# ADC.net
KiCad netlist of a schematic drawn in Altium Designer
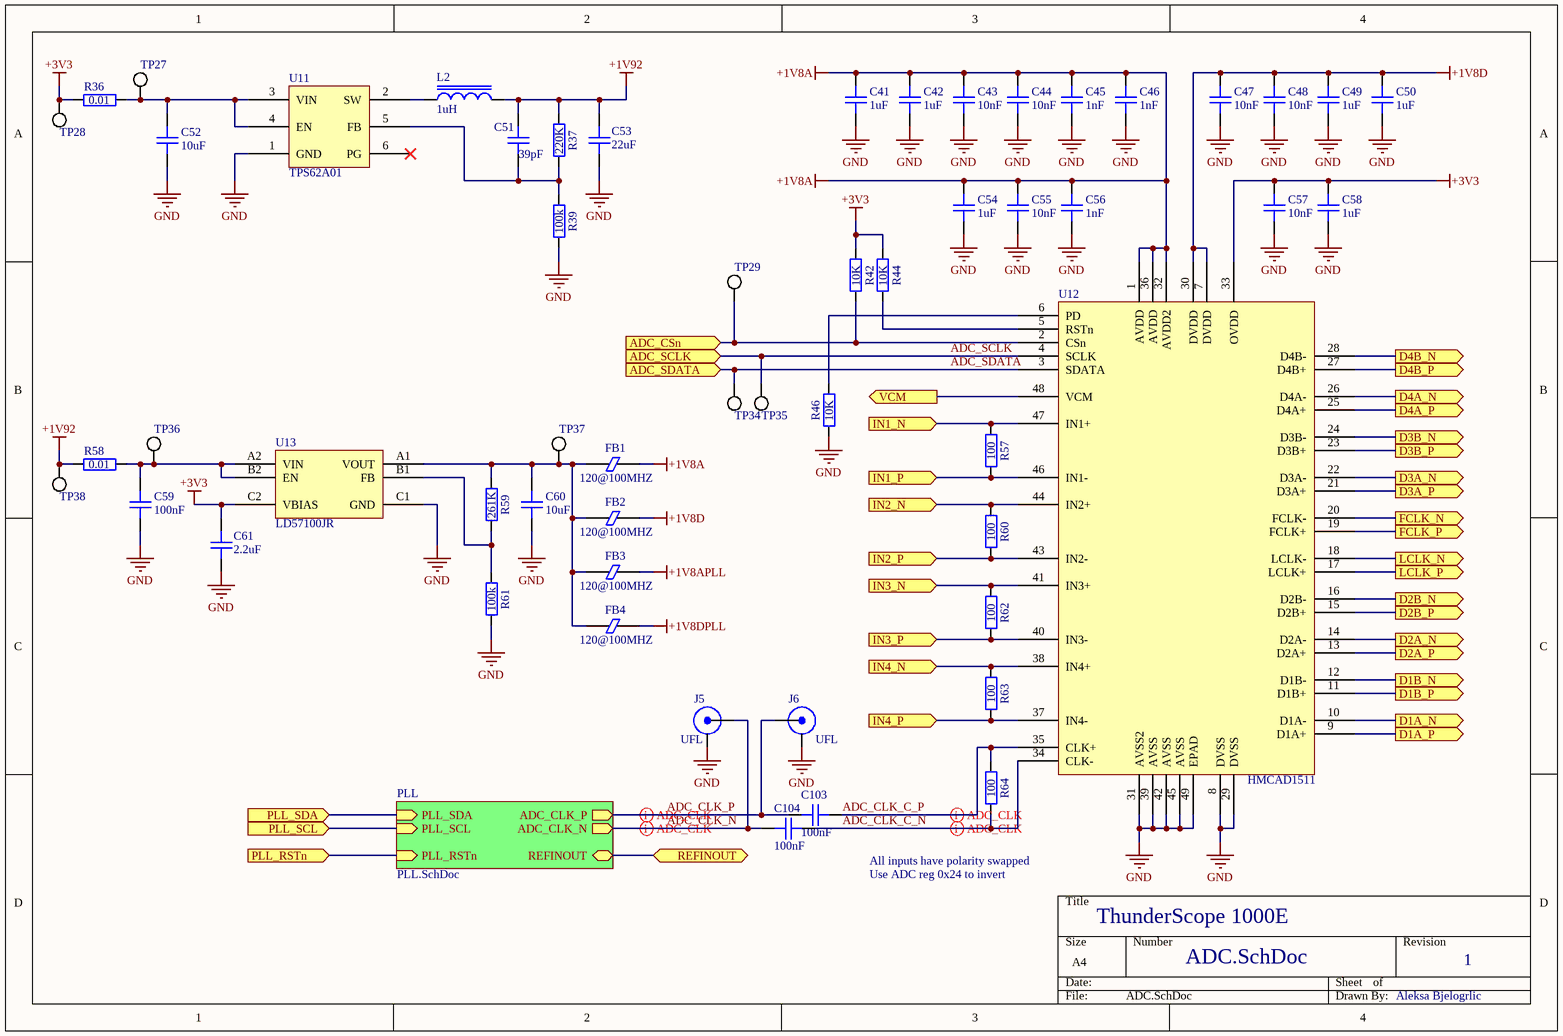
[diagram p0: ADC.SchDoc]

(export (version "E")
  (design (tool "Eeschema 10.0.6"))
  (components
    (comp (ref "C41")
      (value "1uF")
      (footprint "GEN_C_0402")
      (libsource (lib "DSO") (part "CAP 1uF 25V X5R 0402"))
    )
    (comp (ref "C42")
      (value "1uF")
      (footprint "GEN_C_0402")
      (libsource (lib "DSO") (part "CAP 1uF 25V X5R 0402"))
    )
    (comp (ref "C43")
      (value "10nF")
      (footprint "GEN_C_0402")
      (libsource (lib "DSO") (part "CAP 10nF 50V X7R 0402"))
    )
    (comp (ref "C44")
      (value "10nF")
      (footprint "GEN_C_0402")
      (libsource (lib "DSO") (part "CAP 10nF 50V X7R 0402"))
    )
    (comp (ref "C45")
      (value "1nF")
      (footprint "GEN_C_0402")
      (libsource (lib "DSO") (part "CAP 1nF 50V C0G 0402"))
    )
    (comp (ref "C46")
      (value "1nF")
      (footprint "GEN_C_0402")
      (libsource (lib "DSO") (part "CAP 1nF 50V C0G 0402"))
    )
    (comp (ref "C47")
      (value "10nF")
      (footprint "GEN_C_0402")
      (libsource (lib "DSO") (part "CAP 10nF 50V X7R 0402"))
    )
    (comp (ref "C48")
      (value "10nF")
      (footprint "GEN_C_0402")
      (libsource (lib "DSO") (part "CAP 10nF 50V X7R 0402"))
    )
    (comp (ref "C49")
      (value "1uF")
      (footprint "GEN_C_0402")
      (libsource (lib "DSO") (part "CAP 1uF 25V X5R 0402"))
    )
    (comp (ref "C50")
      (value "1uF")
      (footprint "GEN_C_0402")
      (libsource (lib "DSO") (part "CAP 1uF 25V X5R 0402"))
    )
    (comp (ref "C51")
      (value "39pF")
      (footprint "GEN_C_0402")
      (libsource (lib "DSO") (part "CAP 39pF 50V C0G 0402"))
    )
    (comp (ref "C52")
      (value "10uF")
      (footprint "GEN_C_0603")
      (libsource (lib "DSO") (part "CAP 10uF 10V X5R 0603"))
    )
    (comp (ref "C53")
      (value "22uF")
      (footprint "GEN_C_0805")
      (libsource (lib "DSO") (part "CAP 22uF 25V X5R 0805"))
    )
    (comp (ref "C54")
      (value "1uF")
      (footprint "GEN_C_0402")
      (libsource (lib "DSO") (part "CAP 1uF 25V X5R 0402"))
    )
    (comp (ref "C55")
      (value "10nF")
      (footprint "GEN_C_0402")
      (libsource (lib "DSO") (part "CAP 10nF 50V X7R 0402"))
    )
    (comp (ref "C56")
      (value "1nF")
      (footprint "GEN_C_0402")
      (libsource (lib "DSO") (part "CAP 1nF 50V C0G 0402"))
    )
    (comp (ref "C57")
      (value "10nF")
      (footprint "GEN_C_0402")
      (libsource (lib "DSO") (part "CAP 10nF 50V X7R 0402"))
    )
    (comp (ref "C58")
      (value "1uF")
      (footprint "GEN_C_0402")
      (libsource (lib "DSO") (part "CAP 1uF 25V X5R 0402"))
    )
    (comp (ref "C59")
      (value "100nF")
      (footprint "GEN_C_0402")
      (libsource (lib "DSO") (part "CAP 100nF 16V X7R 0402"))
    )
    (comp (ref "C60")
      (value "10uF")
      (footprint "GEN_C_0603")
      (libsource (lib "DSO") (part "CAP 10uF 10V X5R 0603"))
    )
    (comp (ref "C61")
      (value "2.2uF")
      (footprint "GEN_C_0402")
      (libsource (lib "DSO") (part "CAP 2.2uF 10V X5R 0402"))
    )
    (comp (ref "C103")
      (value "100nF")
      (footprint "GEN_C_0402")
      (libsource (lib "DSO") (part "CAP 100nF 16V X7R 0402"))
    )
    (comp (ref "C104")
      (value "100nF")
      (footprint "GEN_C_0402")
      (libsource (lib "DSO") (part "CAP 100nF 16V X7R 0402"))
    )
    (comp (ref "FB1")
      (value "120@100MHZ")
      (footprint "GEN_R_0402")
      (libsource (lib "DSO") (part "FERRITE BEAD 120 OHM 0402"))
    )
    (comp (ref "FB2")
      (value "120@100MHZ")
      (footprint "GEN_R_0402")
      (libsource (lib "DSO") (part "FERRITE BEAD 120 OHM 0402"))
    )
    (comp (ref "FB3")
      (value "120@100MHZ")
      (footprint "GEN_R_0402")
      (libsource (lib "DSO") (part "FERRITE BEAD 120 OHM 0402"))
    )
    (comp (ref "FB4")
      (value "120@100MHZ")
      (footprint "GEN_R_0402")
      (libsource (lib "DSO") (part "FERRITE BEAD 120 OHM 0402"))
    )
    (comp (ref "J5") (value "UFL") (footprint "TE_2334884-1") (libsource (lib "DSO") (part "UFL Jack SMD")))
    (comp (ref "J6") (value "UFL") (footprint "TE_2334884-1") (libsource (lib "DSO") (part "UFL Jack SMD")))
    (comp (ref "L2")
      (value "1uH")
      (footprint "GEN_L_1210")
      (libsource (lib "DSO") (part "IND 1uH 3.1A 45 MOHM 1210"))
    )
    (comp (ref "R36")
      (value "0.01")
      (footprint "GEN_R_0603")
      (fields (field (name "TOLERANCE") "1%"))
      (libsource (lib "DSO") (part "RES 0.01 OHM 1% 1/4W 0603"))
    )
    (comp (ref "R37")
      (value "220K")
      (footprint "GEN_R_0402")
      (fields (field (name "TOLERANCE") "1%"))
      (libsource (lib "DSO") (part "RES 220K OHM 1% 1/16W 0402"))
    )
    (comp (ref "R39")
      (value "100k")
      (footprint "GEN_R_0402")
      (fields (field (name "TOLERANCE") "1%"))
      (libsource (lib "DSO") (part "RES 100K OHM 1% 1/10W 0402"))
    )
    (comp (ref "R42")
      (value "10K")
      (footprint "GEN_R_0402")
      (fields (field (name "TOLERANCE") "1%"))
      (libsource (lib "DSO") (part "RES 10K OHM 1% 1/10W 0402"))
    )
    (comp (ref "R44")
      (value "10K")
      (footprint "GEN_R_0402")
      (fields (field (name "TOLERANCE") "1%"))
      (libsource (lib "DSO") (part "RES 10K OHM 1% 1/10W 0402"))
    )
    (comp (ref "R46")
      (value "10K")
      (footprint "GEN_R_0402")
      (fields (field (name "TOLERANCE") "1%"))
      (libsource (lib "") (part "RES 10K OHM 1% 1/10W 0402_1"))
    )
    (comp (ref "R57")
      (value "100")
      (footprint "GEN_R_0402")
      (fields (field (name "TOLERANCE") "1%"))
      (libsource (lib "DSO") (part "RES 100 OHM 1% 1/10W 0402"))
    )
    (comp (ref "R58")
      (value "0.01")
      (footprint "GEN_R_0603")
      (fields (field (name "TOLERANCE") "1%"))
      (libsource (lib "DSO") (part "RES 0.01 OHM 1% 1/4W 0603"))
    )
    (comp (ref "R59")
      (value "261K")
      (footprint "GEN_R_0402")
      (fields (field (name "TOLERANCE") "1%"))
      (libsource (lib "DSO") (part "RES 261K OHM 1% 1/16W 0402"))
    )
    (comp (ref "R60")
      (value "100")
      (footprint "GEN_R_0402")
      (fields (field (name "TOLERANCE") "1%"))
      (libsource (lib "DSO") (part "RES 100 OHM 1% 1/10W 0402"))
    )
    (comp (ref "R61")
      (value "100k")
      (footprint "GEN_R_0402")
      (fields (field (name "TOLERANCE") "1%"))
      (libsource (lib "DSO") (part "RES 100K OHM 1% 1/10W 0402"))
    )
    (comp (ref "R62")
      (value "100")
      (footprint "GEN_R_0402")
      (fields (field (name "TOLERANCE") "1%"))
      (libsource (lib "DSO") (part "RES 100 OHM 1% 1/10W 0402"))
    )
    (comp (ref "R63")
      (value "100")
      (footprint "GEN_R_0402")
      (fields (field (name "TOLERANCE") "1%"))
      (libsource (lib "DSO") (part "RES 100 OHM 1% 1/10W 0402"))
    )
    (comp (ref "R64")
      (value "100")
      (footprint "GEN_R_0402")
      (fields (field (name "TOLERANCE") "1%"))
      (libsource (lib "DSO") (part "RES 100 OHM 1% 1/10W 0402"))
    )
    (comp (ref "TP27") (value "PCB") (footprint "GEN_TP_PCB") (libsource (lib "DSO") (part "TP PCB 1mm")))
    (comp (ref "TP28") (value "PCB") (footprint "GEN_TP_PCB") (libsource (lib "DSO") (part "TP PCB 1mm")))
    (comp (ref "TP29") (value "PCB") (footprint "GEN_TP_PCB") (libsource (lib "DSO") (part "TP PCB 1mm")))
    (comp (ref "TP34") (value "PCB") (footprint "GEN_TP_PCB") (libsource (lib "DSO") (part "TP PCB 1mm")))
    (comp (ref "TP35") (value "PCB") (footprint "GEN_TP_PCB") (libsource (lib "DSO") (part "TP PCB 1mm")))
    (comp (ref "TP36") (value "PCB") (footprint "GEN_TP_PCB") (libsource (lib "DSO") (part "TP PCB 1mm")))
    (comp (ref "TP37") (value "PCB") (footprint "GEN_TP_PCB") (libsource (lib "DSO") (part "TP PCB 1mm")))
    (comp (ref "TP38") (value "PCB") (footprint "GEN_TP_PCB") (libsource (lib "DSO") (part "TP PCB 1mm")))
    (comp (ref "U11")
      (value "TPS62A01")
      (footprint "TI_SOT563_DRL0006A")
      (libsource (lib "DSO") (part "IC BUCK TPS62A01"))
    )
    (comp (ref "U12")
      (value "HMCAD1511")
      (footprint "AD_QFN48_LP7")
      (libsource (lib "DSO") (part "IC ADC HMCAD1511"))
    )
    (comp (ref "U13")
      (value "LD57100JR")
      (footprint "ST_FlipChip6")
      (libsource (lib "DSO") (part "IC LDO LD57100JR"))
    )
  )
  (nets
    (net (code "1") (name "+1V8A") (class "Default")
      (node (ref "C41") (pin "2") (pinfunction "2_2") (pintype "passive"))
      (node (ref "C42") (pin "2") (pinfunction "2_2") (pintype "passive"))
      (node (ref "C43") (pin "2") (pinfunction "2_2") (pintype "passive"))
      (node (ref "C44") (pin "2") (pinfunction "2_2") (pintype "passive"))
      (node (ref "C45") (pin "2") (pinfunction "2_2") (pintype "passive"))
      (node (ref "C46") (pin "2") (pinfunction "2_2") (pintype "passive"))
      (node (ref "C54") (pin "2") (pinfunction "2_2") (pintype "passive"))
      (node (ref "C55") (pin "2") (pinfunction "2_2") (pintype "passive"))
      (node (ref "C56") (pin "2") (pinfunction "2_2") (pintype "passive"))
      (node (ref "FB1") (pin "2") (pinfunction "2_2") (pintype "passive"))
      (node (ref "U12") (pin "1") (pinfunction "AVDD_1") (pintype "passive"))
      (node (ref "U12") (pin "32") (pinfunction "AVDD2_32") (pintype "passive"))
      (node (ref "U12") (pin "36") (pinfunction "AVDD_36") (pintype "passive"))
    )
    (net (code "2") (name "+1V8APLL") (class "Default")
      (node (ref "FB3") (pin "2") (pinfunction "2_2") (pintype "passive"))
    )
    (net (code "3") (name "+1V8D") (class "Default")
      (node (ref "C47") (pin "2") (pinfunction "2_2") (pintype "passive"))
      (node (ref "C48") (pin "2") (pinfunction "2_2") (pintype "passive"))
      (node (ref "C49") (pin "2") (pinfunction "2_2") (pintype "passive"))
      (node (ref "C50") (pin "2") (pinfunction "2_2") (pintype "passive"))
      (node (ref "FB2") (pin "2") (pinfunction "2_2") (pintype "passive"))
      (node (ref "U12") (pin "30") (pinfunction "DVDD_30") (pintype "passive"))
      (node (ref "U12") (pin "7") (pinfunction "DVDD_7") (pintype "passive"))
    )
    (net (code "4") (name "+1V8DPLL") (class "Default")
      (node (ref "FB4") (pin "2") (pinfunction "2_2") (pintype "passive"))
    )
    (net (code "5") (name "+1V92") (class "Default")
      (node (ref "C51") (pin "2") (pinfunction "2_2") (pintype "passive"))
      (node (ref "C53") (pin "2") (pinfunction "2_2") (pintype "passive"))
      (node (ref "L2") (pin "2") (pinfunction "2_2") (pintype "passive"))
      (node (ref "R37") (pin "2") (pinfunction "2_2") (pintype "passive"))
      (node (ref "R58") (pin "1") (pinfunction "1_1") (pintype "passive"))
      (node (ref "TP38") (pin "1") (pinfunction "1_1") (pintype "passive"))
    )
    (net (code "6") (name "+3V3") (class "Default")
      (node (ref "C57") (pin "2") (pinfunction "2_2") (pintype "passive"))
      (node (ref "C58") (pin "2") (pinfunction "2_2") (pintype "passive"))
      (node (ref "C61") (pin "2") (pinfunction "2_2") (pintype "passive"))
      (node (ref "R36") (pin "1") (pinfunction "1_1") (pintype "passive"))
      (node (ref "R42") (pin "2") (pinfunction "2_2") (pintype "passive"))
      (node (ref "R44") (pin "2") (pinfunction "2_2") (pintype "passive"))
      (node (ref "TP28") (pin "1") (pinfunction "1_1") (pintype "passive"))
      (node (ref "U12") (pin "33") (pinfunction "OVDD_33") (pintype "passive"))
      (node (ref "U13") (pin "C2") (pinfunction "VBIAS_C2") (pintype "passive"))
    )
    (net (code "7") (name "/ADC_CLK_C_N") (class "Default")
      (node (ref "C104") (pin "1") (pinfunction "1_1") (pintype "passive"))
      (node (ref "R64") (pin "1") (pinfunction "1_1") (pintype "passive"))
      (node (ref "U12") (pin "34") (pinfunction "CLK-_34") (pintype "passive"))
    )
    (net (code "8") (name "/ADC_CLK_C_P") (class "Default")
      (node (ref "C103") (pin "1") (pinfunction "1_1") (pintype "passive"))
      (node (ref "R64") (pin "2") (pinfunction "2_2") (pintype "passive"))
      (node (ref "U12") (pin "35") (pinfunction "CLK+_35") (pintype "passive"))
    )
    (net (code "9") (name "/ADC_CLK_N") (class "Default")
      (node (ref "C104") (pin "2") (pinfunction "2_2") (pintype "passive"))
      (node (ref "J5") (pin "1") (pinfunction "Signal_1") (pintype "passive"))
    )
    (net (code "10") (name "/ADC_CLK_P") (class "Default")
      (node (ref "C103") (pin "2") (pinfunction "2_2") (pintype "passive"))
      (node (ref "J6") (pin "1") (pinfunction "Signal_1") (pintype "passive"))
    )
    (net (code "11") (name "/ADC_CSn") (class "Default")
      (node (ref "R42") (pin "1") (pinfunction "1_1") (pintype "passive"))
      (node (ref "TP29") (pin "1") (pinfunction "1_1") (pintype "passive"))
      (node (ref "U12") (pin "2") (pinfunction "CSn_2") (pintype "passive"))
    )
    (net (code "12") (name "/ADC_SCLK") (class "Default")
      (node (ref "TP35") (pin "1") (pinfunction "1_1") (pintype "passive"))
      (node (ref "U12") (pin "4") (pinfunction "SCLK_4") (pintype "passive"))
    )
    (net (code "13") (name "/ADC_SDATA") (class "Default")
      (node (ref "TP34") (pin "1") (pinfunction "1_1") (pintype "passive"))
      (node (ref "U12") (pin "3") (pinfunction "SDATA_3") (pintype "passive"))
    )
    (net (code "14") (name "/D1A_N") (class "Default")
      (node (ref "U12") (pin "10") (pinfunction "D1A-_10") (pintype "passive"))
    )
    (net (code "15") (name "/D1A_P") (class "Default")
      (node (ref "U12") (pin "9") (pinfunction "D1A+_9") (pintype "passive"))
    )
    (net (code "16") (name "/D1B_N") (class "Default")
      (node (ref "U12") (pin "12") (pinfunction "D1B-_12") (pintype "passive"))
    )
    (net (code "17") (name "/D1B_P") (class "Default")
      (node (ref "U12") (pin "11") (pinfunction "D1B+_11") (pintype "passive"))
    )
    (net (code "18") (name "/D2A_N") (class "Default")
      (node (ref "U12") (pin "14") (pinfunction "D2A-_14") (pintype "passive"))
    )
    (net (code "19") (name "/D2A_P") (class "Default")
      (node (ref "U12") (pin "13") (pinfunction "D2A+_13") (pintype "passive"))
    )
    (net (code "20") (name "/D2B_N") (class "Default")
      (node (ref "U12") (pin "16") (pinfunction "D2B-_16") (pintype "passive"))
    )
    (net (code "21") (name "/D2B_P") (class "Default")
      (node (ref "U12") (pin "15") (pinfunction "D2B+_15") (pintype "passive"))
    )
    (net (code "22") (name "/D3A_N") (class "Default")
      (node (ref "U12") (pin "22") (pinfunction "D3A-_22") (pintype "passive"))
    )
    (net (code "23") (name "/D3A_P") (class "Default")
      (node (ref "U12") (pin "21") (pinfunction "D3A+_21") (pintype "passive"))
    )
    (net (code "24") (name "/D3B_N") (class "Default")
      (node (ref "U12") (pin "24") (pinfunction "D3B-_24") (pintype "passive"))
    )
    (net (code "25") (name "/D3B_P") (class "Default")
      (node (ref "U12") (pin "23") (pinfunction "D3B+_23") (pintype "passive"))
    )
    (net (code "26") (name "/D4A_N") (class "Default")
      (node (ref "U12") (pin "26") (pinfunction "D4A-_26") (pintype "passive"))
    )
    (net (code "27") (name "/D4A_P") (class "Default")
      (node (ref "U12") (pin "25") (pinfunction "D4A+_25") (pintype "passive"))
    )
    (net (code "28") (name "/D4B_N") (class "Default")
      (node (ref "U12") (pin "28") (pinfunction "D4B-_28") (pintype "passive"))
    )
    (net (code "29") (name "/D4B_P") (class "Default")
      (node (ref "U12") (pin "27") (pinfunction "D4B+_27") (pintype "passive"))
    )
    (net (code "30") (name "/FCLK_N") (class "Default")
      (node (ref "U12") (pin "20") (pinfunction "FCLK-_20") (pintype "passive"))
    )
    (net (code "31") (name "/FCLK_P") (class "Default")
      (node (ref "U12") (pin "19") (pinfunction "FCLK+_19") (pintype "passive"))
    )
    (net (code "32") (name "/IN1_N") (class "Default")
      (node (ref "R57") (pin "2") (pinfunction "2_2") (pintype "passive"))
      (node (ref "U12") (pin "47") (pinfunction "IN1+_47") (pintype "passive"))
    )
    (net (code "33") (name "/IN1_P") (class "Default")
      (node (ref "R57") (pin "1") (pinfunction "1_1") (pintype "passive"))
      (node (ref "U12") (pin "46") (pinfunction "IN1-_46") (pintype "passive"))
    )
    (net (code "34") (name "/IN2_N") (class "Default")
      (node (ref "R60") (pin "2") (pinfunction "2_2") (pintype "passive"))
      (node (ref "U12") (pin "44") (pinfunction "IN2+_44") (pintype "passive"))
    )
    (net (code "35") (name "/IN2_P") (class "Default")
      (node (ref "R60") (pin "1") (pinfunction "1_1") (pintype "passive"))
      (node (ref "U12") (pin "43") (pinfunction "IN2-_43") (pintype "passive"))
    )
    (net (code "36") (name "/IN3_N") (class "Default")
      (node (ref "R62") (pin "2") (pinfunction "2_2") (pintype "passive"))
      (node (ref "U12") (pin "41") (pinfunction "IN3+_41") (pintype "passive"))
    )
    (net (code "37") (name "/IN3_P") (class "Default")
      (node (ref "R62") (pin "1") (pinfunction "1_1") (pintype "passive"))
      (node (ref "U12") (pin "40") (pinfunction "IN3-_40") (pintype "passive"))
    )
    (net (code "38") (name "/IN4_N") (class "Default")
      (node (ref "R63") (pin "2") (pinfunction "2_2") (pintype "passive"))
      (node (ref "U12") (pin "38") (pinfunction "IN4+_38") (pintype "passive"))
    )
    (net (code "39") (name "/IN4_P") (class "Default")
      (node (ref "R63") (pin "1") (pinfunction "1_1") (pintype "passive"))
      (node (ref "U12") (pin "37") (pinfunction "IN4-_37") (pintype "passive"))
    )
    (net (code "40") (name "/LCLK_N") (class "Default")
      (node (ref "U12") (pin "18") (pinfunction "LCLK-_18") (pintype "passive"))
    )
    (net (code "41") (name "/LCLK_P") (class "Default")
      (node (ref "U12") (pin "17") (pinfunction "LCLK+_17") (pintype "passive"))
    )
    (net (code "46") (name "/VCM") (class "Default")
      (node (ref "U12") (pin "48") (pinfunction "VCM_48") (pintype "passive"))
    )
    (net (code "47") (name "GND") (class "Default")
      (node (ref "C41") (pin "1") (pinfunction "1_1") (pintype "passive"))
      (node (ref "C42") (pin "1") (pinfunction "1_1") (pintype "passive"))
      (node (ref "C43") (pin "1") (pinfunction "1_1") (pintype "passive"))
      (node (ref "C44") (pin "1") (pinfunction "1_1") (pintype "passive"))
      (node (ref "C45") (pin "1") (pinfunction "1_1") (pintype "passive"))
      (node (ref "C46") (pin "1") (pinfunction "1_1") (pintype "passive"))
      (node (ref "C47") (pin "1") (pinfunction "1_1") (pintype "passive"))
      (node (ref "C48") (pin "1") (pinfunction "1_1") (pintype "passive"))
      (node (ref "C49") (pin "1") (pinfunction "1_1") (pintype "passive"))
      (node (ref "C50") (pin "1") (pinfunction "1_1") (pintype "passive"))
      (node (ref "C52") (pin "1") (pinfunction "1_1") (pintype "passive"))
      (node (ref "C53") (pin "1") (pinfunction "1_1") (pintype "passive"))
      (node (ref "C54") (pin "1") (pinfunction "1_1") (pintype "passive"))
      (node (ref "C55") (pin "1") (pinfunction "1_1") (pintype "passive"))
      (node (ref "C56") (pin "1") (pinfunction "1_1") (pintype "passive"))
      (node (ref "C57") (pin "1") (pinfunction "1_1") (pintype "passive"))
      (node (ref "C58") (pin "1") (pinfunction "1_1") (pintype "passive"))
      (node (ref "C59") (pin "1") (pinfunction "1_1") (pintype "passive"))
      (node (ref "C60") (pin "1") (pinfunction "1_1") (pintype "passive"))
      (node (ref "C61") (pin "1") (pinfunction "1_1") (pintype "passive"))
      (node (ref "J5") (pin "2") (pinfunction "SHIELD_2") (pintype "passive"))
      (node (ref "J6") (pin "2") (pinfunction "SHIELD_2") (pintype "passive"))
      (node (ref "R39") (pin "1") (pinfunction "1_1") (pintype "passive"))
      (node (ref "R46") (pin "2") (pinfunction "2_2") (pintype "passive"))
      (node (ref "R61") (pin "1") (pinfunction "1_1") (pintype "passive"))
      (node (ref "U11") (pin "1") (pinfunction "GND_1") (pintype "power_in"))
      (node (ref "U12") (pin "29") (pinfunction "DVSS_29") (pintype "passive"))
      (node (ref "U12") (pin "31") (pinfunction "AVSS2_31") (pintype "passive"))
      (node (ref "U12") (pin "39") (pinfunction "AVSS_39") (pintype "passive"))
      (node (ref "U12") (pin "42") (pinfunction "AVSS_42") (pintype "passive"))
      (node (ref "U12") (pin "45") (pinfunction "AVSS_45") (pintype "passive"))
      (node (ref "U12") (pin "49") (pinfunction "EPAD_49") (pintype "passive"))
      (node (ref "U12") (pin "8") (pinfunction "DVSS_8") (pintype "passive"))
      (node (ref "U13") (pin "C1") (pinfunction "GND_C1") (pintype "passive"))
    )
    (net (code "48") (name "Net-(U11-EN)") (class "Default")
      (node (ref "C52") (pin "2") (pinfunction "2_2") (pintype "passive"))
      (node (ref "R36") (pin "2") (pinfunction "2_2") (pintype "passive"))
      (node (ref "TP27") (pin "1") (pinfunction "1_1") (pintype "passive"))
      (node (ref "U11") (pin "3") (pinfunction "VIN_3") (pintype "power_in"))
      (node (ref "U11") (pin "4") (pinfunction "EN_4") (pintype "passive"))
    )
    (net (code "49") (name "Net-(U11-FB)") (class "Default")
      (node (ref "C51") (pin "1") (pinfunction "1_1") (pintype "passive"))
      (node (ref "R37") (pin "1") (pinfunction "1_1") (pintype "passive"))
      (node (ref "R39") (pin "2") (pinfunction "2_2") (pintype "passive"))
      (node (ref "U11") (pin "5") (pinfunction "FB_5") (pintype "passive"))
    )
    (net (code "50") (name "Net-(U11-SW)") (class "Default")
      (node (ref "L2") (pin "1") (pinfunction "1_1") (pintype "passive"))
      (node (ref "U11") (pin "2") (pinfunction "SW_2") (pintype "passive"))
    )
    (net (code "51") (name "Net-(U12-PD)") (class "Default")
      (node (ref "R46") (pin "1") (pinfunction "1_1") (pintype "passive"))
      (node (ref "U12") (pin "6") (pinfunction "PD_6") (pintype "passive"))
    )
    (net (code "52") (name "Net-(U12-RSTn)") (class "Default")
      (node (ref "R44") (pin "1") (pinfunction "1_1") (pintype "passive"))
      (node (ref "U12") (pin "5") (pinfunction "RSTn_5") (pintype "passive"))
    )
    (net (code "53") (name "Net-(U13-EN)") (class "Default")
      (node (ref "C59") (pin "2") (pinfunction "2_2") (pintype "passive"))
      (node (ref "R58") (pin "2") (pinfunction "2_2") (pintype "passive"))
      (node (ref "TP36") (pin "1") (pinfunction "1_1") (pintype "passive"))
      (node (ref "U13") (pin "A2") (pinfunction "VIN_A2") (pintype "passive"))
      (node (ref "U13") (pin "B2") (pinfunction "EN_B2") (pintype "passive"))
    )
    (net (code "54") (name "Net-(U13-FB)") (class "Default")
      (node (ref "R59") (pin "1") (pinfunction "1_1") (pintype "passive"))
      (node (ref "R61") (pin "2") (pinfunction "2_2") (pintype "passive"))
      (node (ref "U13") (pin "B1") (pinfunction "FB_B1") (pintype "passive"))
    )
    (net (code "55") (name "Net-(U13-VOUT)") (class "Default")
      (node (ref "C60") (pin "2") (pinfunction "2_2") (pintype "passive"))
      (node (ref "FB1") (pin "1") (pinfunction "1_1") (pintype "passive"))
      (node (ref "FB2") (pin "1") (pinfunction "1_1") (pintype "passive"))
      (node (ref "FB3") (pin "1") (pinfunction "1_1") (pintype "passive"))
      (node (ref "FB4") (pin "1") (pinfunction "1_1") (pintype "passive"))
      (node (ref "R59") (pin "2") (pinfunction "2_2") (pintype "passive"))
      (node (ref "TP37") (pin "1") (pinfunction "1_1") (pintype "passive"))
      (node (ref "U13") (pin "A1") (pinfunction "VOUT_A1") (pintype "passive"))
    )
    (net (code "56") (name "unconnected-(U11-PG-Pad6)") (class "Default")
      (node (ref "U11") (pin "6") (pinfunction "PG_6") (pintype "passive+no_connect"))
    )
  )
)
